# Micro_Controller.net
KiCad netlist of a schematic drawn in Altium Designer
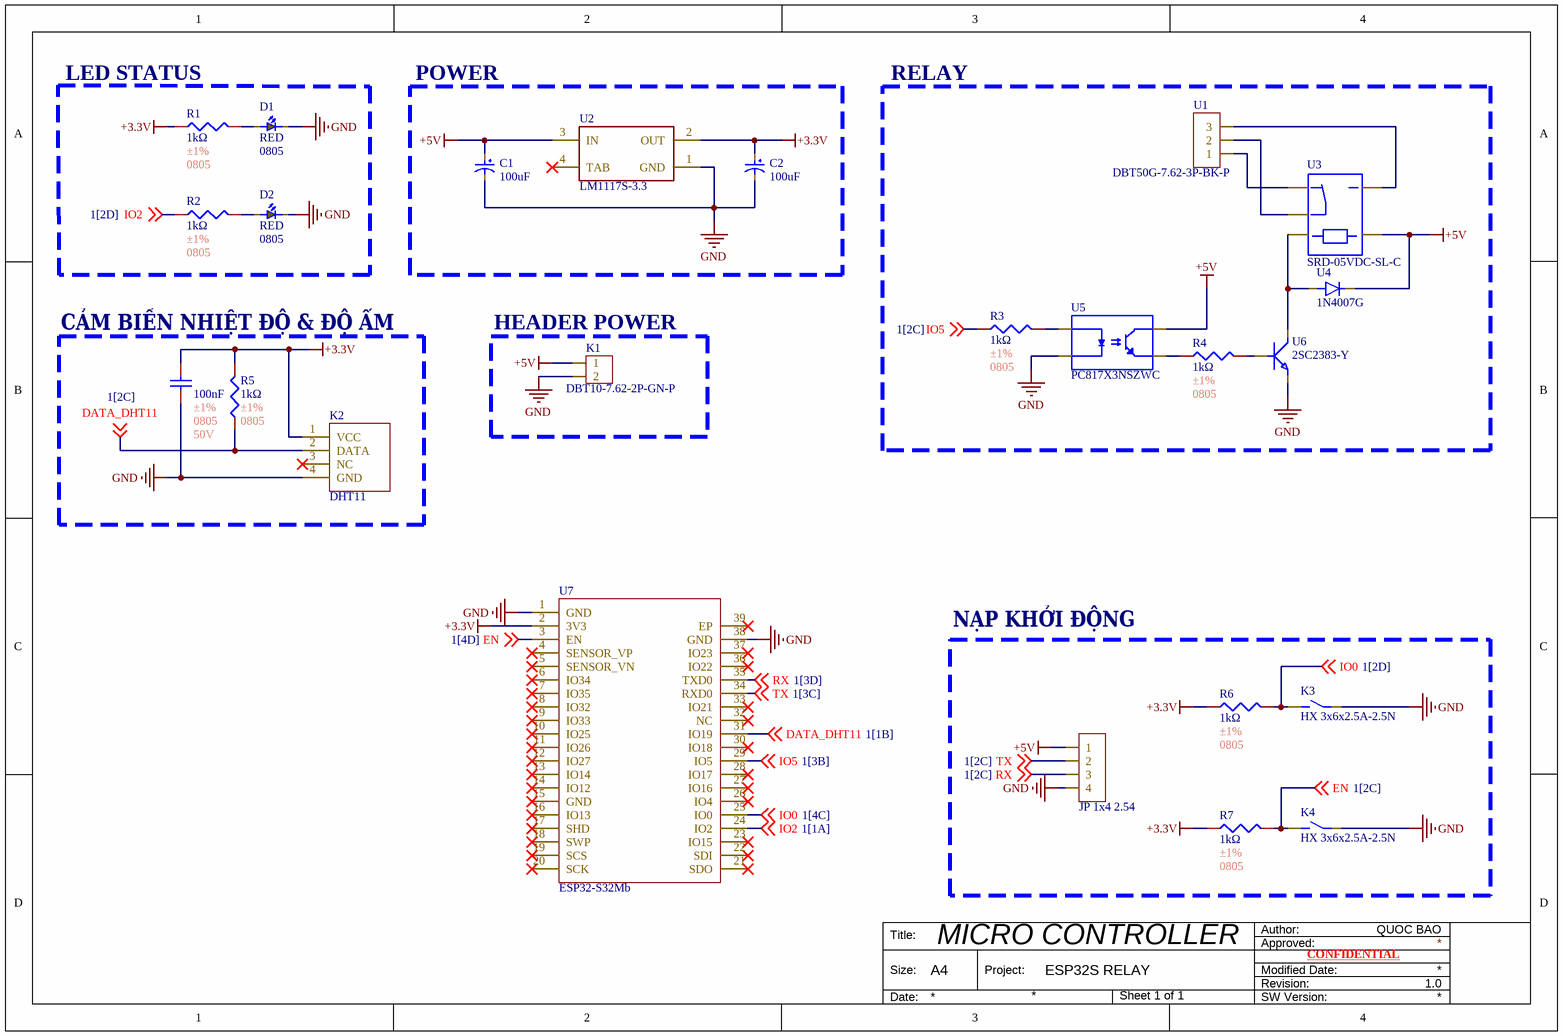
[diagram p0: Micro Controller.SchDoc]

(export (version "E")
  (design (tool "Eeschema 10.0.6"))
  (components
    (comp (ref "C1")
      (value "100uF")
      (footprint "C_TH_8x11.5")
      (description "3.5mm 100uF 50V ±20% Through Hole,D8xL11.5mm Aluminum Electrolytic Capacitors RoHS")
      (fields (field (name "MANUFACTURER") "Rubycon") (field (name "MFR. PART #") "50YXF100MEFC8X11.5"))
      (libsource (lib "Quoc_Bao") (part "C_100uF_8x11.5_TH"))
    )
    (comp (ref "C2")
      (value "100uF")
      (footprint "C_TH_8x11.5")
      (description "3.5mm 100uF 50V ±20% Through Hole,D8xL11.5mm Aluminum Electrolytic Capacitors RoHS")
      (fields (field (name "MANUFACTURER") "Rubycon") (field (name "MFR. PART #") "50YXF100MEFC8X11.5"))
      (libsource (lib "Quoc_Bao") (part "C_100uF_8x11.5_TH"))
    )
    (comp (ref "C3")
      (value "100nF")
      (footprint "C0805")
      (description "50V 10pF NP0 ±1% 0402 Multilayer Ceramic Capacitors MLCC - SMD/SMT ROHS")
      (fields
        (field (name "MANUFACTURER") "YAGEO")
        (field (name "MFR. PART #") "CC0402FRNPO9BN100")
        (field (name "TOLERANCE") "±1%")
        (field (name "PACKAGE") "0805")
        (field (name "VOLTAGE RATING") "50V")
      )
      (libsource (lib "Quoc_Bao") (part "C0805_100nF_±1%"))
    )
    (comp (ref "D1")
      (value "RED")
      (footprint "LED0805")
      (description "25mcd~40mcd Water Clear -40℃~+85℃ 624nm Red 120° 60mW 0402 LED Indication - Discrete ROHS")
      (fields
        (field (name "MANUFACTURER") "XINGLIGHT")
        (field (name "MFR. PART #") "XL-1005UGC")
        (field (name "PACKAGE") "0805")
      )
      (libsource (lib "Quoc_Bao") (part "D0805_RED"))
    )
    (comp (ref "D2")
      (value "RED")
      (footprint "LED0805")
      (description "25mcd~40mcd Water Clear -40℃~+85℃ 624nm Red 120° 60mW 0402 LED Indication - Discrete ROHS")
      (fields
        (field (name "MANUFACTURER") "XINGLIGHT")
        (field (name "MFR. PART #") "XL-1005UGC")
        (field (name "PACKAGE") "0805")
      )
      (libsource (lib "Quoc_Bao") (part "D0805_RED"))
    )
    (comp (ref "JP1")
      (value "JP 1x4 2.54")
      (footprint "JP 1X4 DT")
      (description "Cắm")
      (libsource (lib "Quoc_Bao") (part "JP 1x4 2.54 Cai Thang"))
    )
    (comp (ref "K1")
      (value "DBT10-7.62-2P-GN-P")
      (footprint "DBT10-7.62-2P-GN-P")
      (fields (field (name "MANUFACTURER") "DORABO") (field (name "LCSC PART #") "C395930"))
      (libsource (lib "Quoc_Bao") (part "DBT10-7.62-2P-GN-P"))
    )
    (comp (ref "K2")
      (value "DHT11")
      (footprint "DHT11")
      (description "±5%RH -20℃~+60℃ 5%RH~95%RH SIP-4 Humidity, Moisture Sensors RoHS")
      (fields (field (name "MANUFACTURER") "Aosong") (field (name "LCSC PART #") "C117051"))
      (libsource (lib "Quoc_Bao") (part "DHT11"))
    )
    (comp (ref "K3")
      (value "HX 3x6x2.5A-2.5N")
      (footprint "HX 3x6x2.5A-2.5N")
      (description "Without Bracket 6mm 12V 3.6mm Square Button No SPST 50mA SMD,6x3mm Tactile Switches RoHS")
      (fields (field (name "MANUFACTURER") "hanxia") (field (name "LCSC PART #") "C36498960"))
      (libsource (lib "Quoc_Bao") (part "HX 3x6x2.5A-2.5N"))
    )
    (comp (ref "K4")
      (value "HX 3x6x2.5A-2.5N")
      (footprint "HX 3x6x2.5A-2.5N")
      (description "Without Bracket 6mm 12V 3.6mm Square Button No SPST 50mA SMD,6x3mm Tactile Switches RoHS")
      (fields (field (name "MANUFACTURER") "hanxia") (field (name "LCSC PART #") "C36498960"))
      (libsource (lib "Quoc_Bao") (part "HX 3x6x2.5A-2.5N"))
    )
    (comp (ref "R1")
      (value "1kΩ")
      (footprint "R0805")
      (description "62.5mW Thick Film Resistor 50V ±1% ±200ppm/℃ 10Ω 0402 Chip Resistor - Surface Mount ROHS")
      (fields
        (field (name "MANUFACTURER") "YAGEO")
        (field (name "MFR. PART #") "RC0805FR-0710RL")
        (field (name "TOLERANCE") "±1%")
        (field (name "PACKAGE") "0805")
      )
      (libsource (lib "Quoc_Bao") (part "R0805_1kΩ_±1%"))
    )
    (comp (ref "R2")
      (value "1kΩ")
      (footprint "R0805")
      (description "62.5mW Thick Film Resistor 50V ±1% ±200ppm/℃ 10Ω 0402 Chip Resistor - Surface Mount ROHS")
      (fields
        (field (name "MANUFACTURER") "YAGEO")
        (field (name "MFR. PART #") "RC0805FR-0710RL")
        (field (name "TOLERANCE") "±1%")
        (field (name "PACKAGE") "0805")
      )
      (libsource (lib "Quoc_Bao") (part "R0805_1kΩ_±1%"))
    )
    (comp (ref "R3")
      (value "1kΩ")
      (footprint "R0805")
      (description "62.5mW Thick Film Resistor 50V ±1% ±200ppm/℃ 10Ω 0402 Chip Resistor - Surface Mount ROHS")
      (fields
        (field (name "MANUFACTURER") "YAGEO")
        (field (name "MFR. PART #") "RC0805FR-0710RL")
        (field (name "TOLERANCE") "±1%")
        (field (name "PACKAGE") "0805")
      )
      (libsource (lib "Quoc_Bao") (part "R0805_1kΩ_±1%"))
    )
    (comp (ref "R4")
      (value "1kΩ")
      (footprint "R0805")
      (description "62.5mW Thick Film Resistor 50V ±1% ±200ppm/℃ 10Ω 0402 Chip Resistor - Surface Mount ROHS")
      (fields
        (field (name "MANUFACTURER") "YAGEO")
        (field (name "MFR. PART #") "RC0805FR-0710RL")
        (field (name "TOLERANCE") "±1%")
        (field (name "PACKAGE") "0805")
      )
      (libsource (lib "Quoc_Bao") (part "R0805_1kΩ_±1%"))
    )
    (comp (ref "R5")
      (value "1kΩ")
      (footprint "R0805")
      (description "62.5mW Thick Film Resistor 50V ±1% ±200ppm/℃ 10Ω 0402 Chip Resistor - Surface Mount ROHS")
      (fields
        (field (name "MANUFACTURER") "YAGEO")
        (field (name "MFR. PART #") "RC0805FR-0710RL")
        (field (name "TOLERANCE") "±1%")
        (field (name "PACKAGE") "0805")
      )
      (libsource (lib "Quoc_Bao") (part "R0805_1kΩ_±1%"))
    )
    (comp (ref "R6")
      (value "1kΩ")
      (footprint "R0805")
      (description "62.5mW Thick Film Resistor 50V ±1% ±200ppm/℃ 10Ω 0402 Chip Resistor - Surface Mount ROHS")
      (fields
        (field (name "MANUFACTURER") "YAGEO")
        (field (name "MFR. PART #") "RC0805FR-0710RL")
        (field (name "TOLERANCE") "±1%")
        (field (name "PACKAGE") "0805")
      )
      (libsource (lib "Quoc_Bao") (part "R0805_1kΩ_±1%"))
    )
    (comp (ref "R7")
      (value "1kΩ")
      (footprint "R0805")
      (description "62.5mW Thick Film Resistor 50V ±1% ±200ppm/℃ 10Ω 0402 Chip Resistor - Surface Mount ROHS")
      (fields
        (field (name "MANUFACTURER") "YAGEO")
        (field (name "MFR. PART #") "RC0805FR-0710RL")
        (field (name "TOLERANCE") "±1%")
        (field (name "PACKAGE") "0805")
      )
      (libsource (lib "Quoc_Bao") (part "R0805_1kΩ_±1%"))
    )
    (comp (ref "U1")
      (value "DBT50G-7.62-3P-BK-P")
      (footprint "DBT50G-7.62-3P-BK-P")
      (fields (field (name "MANUFACTURER") "DORABO") (field (name "LCSC PART #") "C496128"))
      (libsource (lib "Quoc_Bao") (part "DBT50G-7.62-3P-BK-P"))
    )
    (comp (ref "U2")
      (value "LM1117S-3.3")
      (footprint "AMS1117-3.3")
      (fields (field (name "MANUFACTURER") "HTC") (field (name "LCSC PART #") "C126027"))
      (libsource (lib "Quoc_Bao") (part "LM1117S-3.3"))
    )
    (comp (ref "U3")
      (value "SRD-05VDC-SL-C")
      (footprint "SRD-05VDC-SL-C")
      (description "250V@AC 5V 15A Through Hole,19.2x15.6mm Power Relays RoHS")
      (fields (field (name "MANUFACTURER") "Songle Relay") (field (name "LCSC PART #") "C35449"))
      (libsource (lib "Quoc_Bao") (part "SRD-05VDC-SL-C"))
    )
    (comp (ref "U4")
      (value "1N4007G")
      (footprint "1N4007G")
      (description "30A 1kV 930mV@1A 1A DO-41 Single Diodes RoHS")
      (fields (field (name "MANUFACTURER") "onsemi") (field (name "LCSC PART #") "C232439"))
      (libsource (lib "Quoc_Bao") (part "1N4007G"))
    )
    (comp (ref "U5")
      (value "PC817X3NSZWC")
      (footprint "PC817X3NSZWC")
      (description "50mA 100mV@20mA,1mA 80V 6V DC DIP-4 Transistor, Photovoltaic Output Optoisolators RoHS")
      (fields (field (name "MANUFACTURER") "SHARP") (field (name "LCSC PART #") "C39832427"))
      (libsource (lib "Quoc_Bao") (part "PC817X3NSZWC"))
    )
    (comp (ref "U6")
      (value "2SC2383-Y")
      (footprint "2SC2383-Y")
      (description "900mW 160V 1A NPN TO-92LM Single Bipolar Transistors RoHS")
      (fields (field (name "MANUFACTURER") "BLUE ROCKET") (field (name "LCSC PART #") "C2844058"))
      (libsource (lib "Quoc_Bao") (part "2SC2383-Y"))
    )
    (comp (ref "U7")
      (value "ESP32-S32Mb")
      (footprint "ESP32-S32Mb")
      (description "2.4GHz ESP32 Chip On-board PCB Antenna -90dBm RF Transceiver Modules and Modems RoHS")
      (fields (field (name "MANUFACTURER") "Ai-Thinker") (field (name "LCSC PART #") "C2764096"))
      (libsource (lib "Quoc_Bao") (part "ESP32-S32Mb"))
    )
  )
  (nets
    (net (code "1") (name "+3.3V") (class "Default")
      (node (ref "C2") (pin "1") (pinfunction "1_1") (pintype "passive"))
      (node (ref "C3") (pin "1") (pinfunction "1_1") (pintype "passive"))
      (node (ref "K2") (pin "1") (pinfunction "VCC_1") (pintype "passive"))
      (node (ref "R1") (pin "1") (pinfunction "1_1") (pintype "passive"))
      (node (ref "R5") (pin "2") (pinfunction "2_2") (pintype "passive"))
      (node (ref "R6") (pin "1") (pinfunction "1_1") (pintype "passive"))
      (node (ref "R7") (pin "1") (pinfunction "1_1") (pintype "passive"))
      (node (ref "U2") (pin "2") (pinfunction "OUT_2") (pintype "passive"))
      (node (ref "U7") (pin "2") (pinfunction "3V3_2") (pintype "passive"))
    )
    (net (code "2") (name "+5V") (class "Default")
      (node (ref "C1") (pin "1") (pinfunction "1_1") (pintype "passive"))
      (node (ref "JP1") (pin "1") (pinfunction "1_1") (pintype "passive"))
      (node (ref "K1") (pin "1") (pinfunction "1_1") (pintype "passive"))
      (node (ref "U2") (pin "3") (pinfunction "IN_3") (pintype "passive"))
      (node (ref "U3") (pin "1") (pinfunction "1_1") (pintype "passive"))
      (node (ref "U4") (pin "1") (pinfunction "C_1") (pintype "passive"))
      (node (ref "U5") (pin "4") (pinfunction "COLLECTOR_4") (pintype "passive"))
    )
    (net (code "3") (name "DATA_DHT11") (class "Default")
      (node (ref "K2") (pin "2") (pinfunction "DATA_2") (pintype "passive"))
      (node (ref "R5") (pin "1") (pinfunction "1_1") (pintype "passive"))
      (node (ref "U7") (pin "31") (pinfunction "IO19_31") (pintype "passive"))
    )
    (net (code "4") (name "EN") (class "Default")
      (node (ref "K4") (pin "1") (pinfunction "1_1") (pintype "passive"))
      (node (ref "R7") (pin "2") (pinfunction "2_2") (pintype "passive"))
      (node (ref "U7") (pin "3") (pinfunction "EN_3") (pintype "passive"))
    )
    (net (code "5") (name "GND") (class "Default")
      (node (ref "C1") (pin "2") (pinfunction "2_2") (pintype "passive"))
      (node (ref "C2") (pin "2") (pinfunction "2_2") (pintype "passive"))
      (node (ref "C3") (pin "2") (pinfunction "2_2") (pintype "passive"))
      (node (ref "D1") (pin "2") (pinfunction "2_2") (pintype "passive"))
      (node (ref "D2") (pin "2") (pinfunction "2_2") (pintype "passive"))
      (node (ref "JP1") (pin "4") (pinfunction "4_4") (pintype "passive"))
      (node (ref "K1") (pin "2") (pinfunction "2_2") (pintype "passive"))
      (node (ref "K2") (pin "4") (pinfunction "GND_4") (pintype "passive"))
      (node (ref "K3") (pin "2") (pinfunction "2_2") (pintype "passive"))
      (node (ref "K4") (pin "2") (pinfunction "2_2") (pintype "passive"))
      (node (ref "U2") (pin "1") (pinfunction "GND_1") (pintype "passive"))
      (node (ref "U5") (pin "2") (pinfunction "CATHODE_2") (pintype "passive"))
      (node (ref "U6") (pin "3") (pinfunction "3_3") (pintype "passive"))
      (node (ref "U7") (pin "1") (pinfunction "GND_1") (pintype "passive"))
      (node (ref "U7") (pin "38") (pinfunction "GND_38") (pintype "passive"))
    )
    (net (code "6") (name "IO0") (class "Default")
      (node (ref "K3") (pin "1") (pinfunction "1_1") (pintype "passive"))
      (node (ref "R6") (pin "2") (pinfunction "2_2") (pintype "passive"))
      (node (ref "U7") (pin "25") (pinfunction "IO0_25") (pintype "passive"))
    )
    (net (code "7") (name "IO2") (class "Default")
      (node (ref "R2") (pin "1") (pinfunction "1_1") (pintype "passive"))
      (node (ref "U7") (pin "24") (pinfunction "IO2_24") (pintype "passive"))
    )
    (net (code "8") (name "IO5") (class "Default")
      (node (ref "R3") (pin "1") (pinfunction "1_1") (pintype "passive"))
      (node (ref "U7") (pin "29") (pinfunction "IO5_29") (pintype "passive"))
    )
    (net (code "9") (name "Net-(D1-Pad1)") (class "Default")
      (node (ref "D1") (pin "1") (pinfunction "1_1") (pintype "passive"))
      (node (ref "R1") (pin "2") (pinfunction "2_2") (pintype "passive"))
    )
    (net (code "10") (name "Net-(D2-Pad1)") (class "Default")
      (node (ref "D2") (pin "1") (pinfunction "1_1") (pintype "passive"))
      (node (ref "R2") (pin "2") (pinfunction "2_2") (pintype "passive"))
    )
    (net (code "11") (name "Net-(R4-Pad2)") (class "Default")
      (node (ref "R4") (pin "2") (pinfunction "2_2") (pintype "passive"))
      (node (ref "U6") (pin "1") (pinfunction "1_1") (pintype "passive"))
    )
    (net (code "12") (name "Net-(U1-Pad1)") (class "Default")
      (node (ref "U1") (pin "1") (pinfunction "1_1") (pintype "passive"))
      (node (ref "U3") (pin "3") (pinfunction "3_3") (pintype "passive"))
    )
    (net (code "13") (name "Net-(U1-Pad2)") (class "Default")
      (node (ref "U1") (pin "2") (pinfunction "2_2") (pintype "passive"))
      (node (ref "U3") (pin "5") (pinfunction "5_5") (pintype "passive"))
    )
    (net (code "14") (name "Net-(U1-Pad3)") (class "Default")
      (node (ref "U1") (pin "3") (pinfunction "3_3") (pintype "passive"))
      (node (ref "U3") (pin "2") (pinfunction "2_2") (pintype "passive"))
    )
    (net (code "15") (name "Net-(U4-A)") (class "Default")
      (node (ref "U3") (pin "4") (pinfunction "4_4") (pintype "passive"))
      (node (ref "U4") (pin "2") (pinfunction "A_2") (pintype "passive"))
      (node (ref "U6") (pin "2") (pinfunction "2_2") (pintype "passive"))
    )
    (net (code "16") (name "Net-(U5-ANODE)") (class "Default")
      (node (ref "R3") (pin "2") (pinfunction "2_2") (pintype "passive"))
      (node (ref "U5") (pin "1") (pinfunction "ANODE_1") (pintype "passive"))
    )
    (net (code "17") (name "Net-(U5-EMITTER)") (class "Default")
      (node (ref "R4") (pin "1") (pinfunction "1_1") (pintype "passive"))
      (node (ref "U5") (pin "3") (pinfunction "EMITTER_3") (pintype "passive"))
    )
    (net (code "18") (name "RX") (class "Default")
      (node (ref "JP1") (pin "3") (pinfunction "3_3") (pintype "passive"))
      (node (ref "U7") (pin "35") (pinfunction "TXD0_35") (pintype "passive"))
    )
    (net (code "19") (name "TX") (class "Default")
      (node (ref "JP1") (pin "2") (pinfunction "2_2") (pintype "passive"))
      (node (ref "U7") (pin "34") (pinfunction "RXD0_34") (pintype "passive"))
    )
    (net (code "20") (name "unconnected-(K2-NC-Pad3)") (class "Default")
      (node (ref "K2") (pin "3") (pinfunction "NC_3") (pintype "passive+no_connect"))
    )
    (net (code "21") (name "unconnected-(U2-TAB-Pad4)") (class "Default")
      (node (ref "U2") (pin "4") (pinfunction "TAB_4") (pintype "passive+no_connect"))
    )
    (net (code "22") (name "unconnected-(U7-EP-Pad39)") (class "Default")
      (node (ref "U7") (pin "39") (pinfunction "EP_39") (pintype "passive+no_connect"))
    )
    (net (code "23") (name "unconnected-(U7-GND-Pad15)") (class "Default")
      (node (ref "U7") (pin "15") (pinfunction "GND_15") (pintype "passive+no_connect"))
    )
    (net (code "24") (name "unconnected-(U7-IO4-Pad26)") (class "Default")
      (node (ref "U7") (pin "26") (pinfunction "IO4_26") (pintype "passive+no_connect"))
    )
    (net (code "25") (name "unconnected-(U7-IO12-Pad14)") (class "Default")
      (node (ref "U7") (pin "14") (pinfunction "IO12_14") (pintype "passive+no_connect"))
    )
    (net (code "26") (name "unconnected-(U7-IO13-Pad16)") (class "Default")
      (node (ref "U7") (pin "16") (pinfunction "IO13_16") (pintype "passive+no_connect"))
    )
    (net (code "27") (name "unconnected-(U7-IO14-Pad13)") (class "Default")
      (node (ref "U7") (pin "13") (pinfunction "IO14_13") (pintype "passive+no_connect"))
    )
    (net (code "28") (name "unconnected-(U7-IO15-Pad23)") (class "Default")
      (node (ref "U7") (pin "23") (pinfunction "IO15_23") (pintype "passive+no_connect"))
    )
    (net (code "29") (name "unconnected-(U7-IO16-Pad27)") (class "Default")
      (node (ref "U7") (pin "27") (pinfunction "IO16_27") (pintype "passive+no_connect"))
    )
    (net (code "30") (name "unconnected-(U7-IO17-Pad28)") (class "Default")
      (node (ref "U7") (pin "28") (pinfunction "IO17_28") (pintype "passive+no_connect"))
    )
    (net (code "31") (name "unconnected-(U7-IO18-Pad30)") (class "Default")
      (node (ref "U7") (pin "30") (pinfunction "IO18_30") (pintype "passive+no_connect"))
    )
    (net (code "32") (name "unconnected-(U7-IO21-Pad33)") (class "Default")
      (node (ref "U7") (pin "33") (pinfunction "IO21_33") (pintype "passive+no_connect"))
    )
    (net (code "33") (name "unconnected-(U7-IO22-Pad36)") (class "Default")
      (node (ref "U7") (pin "36") (pinfunction "IO22_36") (pintype "passive+no_connect"))
    )
    (net (code "34") (name "unconnected-(U7-IO23-Pad37)") (class "Default")
      (node (ref "U7") (pin "37") (pinfunction "IO23_37") (pintype "passive+no_connect"))
    )
    (net (code "35") (name "unconnected-(U7-IO25-Pad10)") (class "Default")
      (node (ref "U7") (pin "10") (pinfunction "IO25_10") (pintype "passive+no_connect"))
    )
    (net (code "36") (name "unconnected-(U7-IO26-Pad11)") (class "Default")
      (node (ref "U7") (pin "11") (pinfunction "IO26_11") (pintype "passive+no_connect"))
    )
    (net (code "37") (name "unconnected-(U7-IO27-Pad12)") (class "Default")
      (node (ref "U7") (pin "12") (pinfunction "IO27_12") (pintype "passive+no_connect"))
    )
    (net (code "38") (name "unconnected-(U7-IO32-Pad8)") (class "Default")
      (node (ref "U7") (pin "8") (pinfunction "IO32_8") (pintype "passive+no_connect"))
    )
    (net (code "39") (name "unconnected-(U7-IO33-Pad9)") (class "Default")
      (node (ref "U7") (pin "9") (pinfunction "IO33_9") (pintype "passive+no_connect"))
    )
    (net (code "40") (name "unconnected-(U7-IO34-Pad6)") (class "Default")
      (node (ref "U7") (pin "6") (pinfunction "IO34_6") (pintype "passive+no_connect"))
    )
    (net (code "41") (name "unconnected-(U7-IO35-Pad7)") (class "Default")
      (node (ref "U7") (pin "7") (pinfunction "IO35_7") (pintype "passive+no_connect"))
    )
    (net (code "42") (name "unconnected-(U7-NC-Pad32)") (class "Default")
      (node (ref "U7") (pin "32") (pinfunction "NC_32") (pintype "passive+no_connect"))
    )
    (net (code "43") (name "unconnected-(U7-SCK-Pad20)") (class "Default")
      (node (ref "U7") (pin "20") (pinfunction "SCK_20") (pintype "passive+no_connect"))
    )
    (net (code "44") (name "unconnected-(U7-SCS-Pad19)") (class "Default")
      (node (ref "U7") (pin "19") (pinfunction "SCS_19") (pintype "passive+no_connect"))
    )
    (net (code "45") (name "unconnected-(U7-SDI-Pad22)") (class "Default")
      (node (ref "U7") (pin "22") (pinfunction "SDI_22") (pintype "passive+no_connect"))
    )
    (net (code "46") (name "unconnected-(U7-SDO-Pad21)") (class "Default")
      (node (ref "U7") (pin "21") (pinfunction "SDO_21") (pintype "passive+no_connect"))
    )
    (net (code "47") (name "unconnected-(U7-SENSOR_VN-Pad5)") (class "Default")
      (node (ref "U7") (pin "5") (pinfunction "SENSOR_VN_5") (pintype "passive+no_connect"))
    )
    (net (code "48") (name "unconnected-(U7-SENSOR_VP-Pad4)") (class "Default")
      (node (ref "U7") (pin "4") (pinfunction "SENSOR_VP_4") (pintype "passive+no_connect"))
    )
    (net (code "49") (name "unconnected-(U7-SHD-Pad17)") (class "Default")
      (node (ref "U7") (pin "17") (pinfunction "SHD_17") (pintype "passive+no_connect"))
    )
    (net (code "50") (name "unconnected-(U7-SWP-Pad18)") (class "Default")
      (node (ref "U7") (pin "18") (pinfunction "SWP_18") (pintype "passive+no_connect"))
    )
  )
)
